# CONNECTOR.net
KiCad netlist of a schematic drawn in Altium Designer
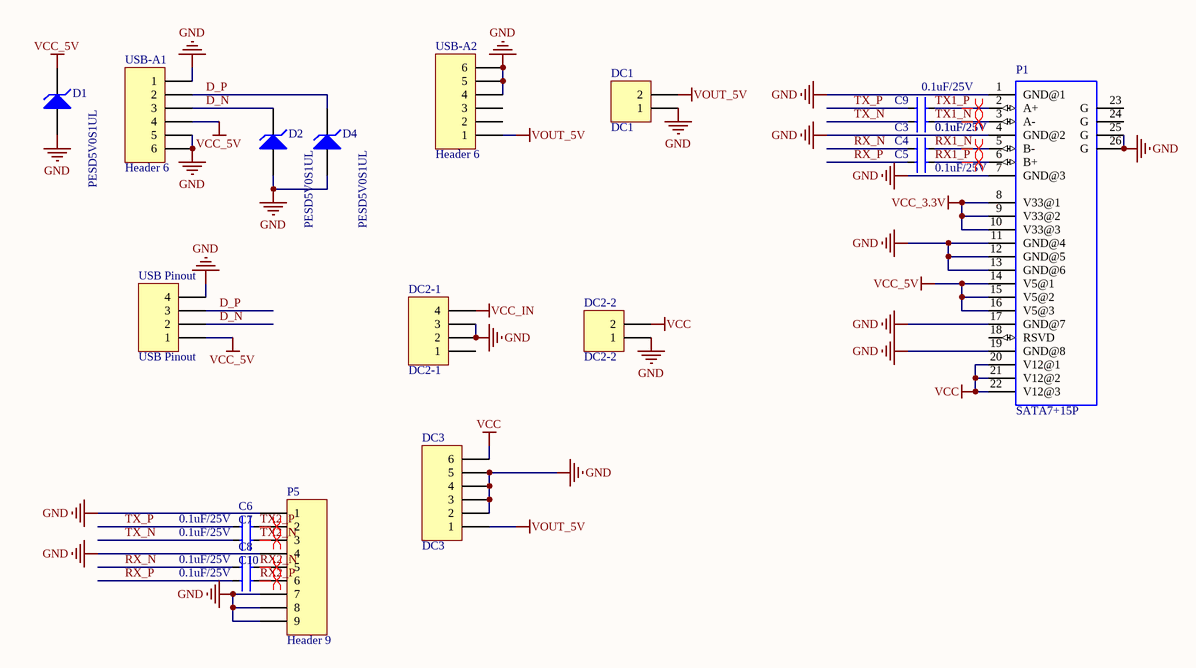
[diagram p0: CONNECTOR.SchDoc]

(export (version "E")
  (design (tool "Eeschema 10.0.6"))
  (components
    (comp (ref "C3")
      (value "0.1uF/25V")
      (footprint "0603C")
      (description "CCX85-103")
      (libsource (lib "无极性电容") (part "0.01UF"))
    )
    (comp (ref "C4")
      (value "0.1uF/25V")
      (footprint "0603C")
      (description "CCX85-103")
      (libsource (lib "无极性电容") (part "0.01UF"))
    )
    (comp (ref "C5")
      (value "0.1uF/25V")
      (footprint "0603C")
      (description "CCX85-103")
      (libsource (lib "无极性电容") (part "0.01UF"))
    )
    (comp (ref "C6")
      (value "0.1uF/25V")
      (footprint "0603C")
      (description "CCX85-103")
      (libsource (lib "无极性电容") (part "0.01UF"))
    )
    (comp (ref "C7")
      (value "0.1uF/25V")
      (footprint "0603C")
      (description "CCX85-103")
      (libsource (lib "无极性电容") (part "0.01UF"))
    )
    (comp (ref "C8")
      (value "0.1uF/25V")
      (footprint "0603C")
      (description "CCX85-103")
      (libsource (lib "无极性电容") (part "0.01UF"))
    )
    (comp (ref "C9")
      (value "0.1uF/25V")
      (footprint "0603C")
      (description "CCX85-103")
      (libsource (lib "无极性电容") (part "0.01UF"))
    )
    (comp (ref "C10")
      (value "0.1uF/25V")
      (footprint "0603C")
      (description "CCX85-103")
      (libsource (lib "无极性电容") (part "0.01UF"))
    )
    (comp (ref "D1")
      (value "PESD5V0S1UL")
      (footprint "0402R")
      (description "Zener Diode")
      (fields (field (name "PUBLISHER") "Altium Limited"))
      (libsource (lib "Miscellaneous Devices") (part "D Zener"))
    )
    (comp (ref "D2")
      (value "PESD5V0S1UL")
      (footprint "0402R")
      (description "Zener Diode")
      (fields (field (name "PUBLISHER") "Altium Limited"))
      (libsource (lib "Miscellaneous Devices") (part "D Zener"))
    )
    (comp (ref "D4")
      (value "PESD5V0S1UL")
      (footprint "0402R")
      (description "Zener Diode")
      (fields (field (name "PUBLISHER") "Altium Limited"))
      (libsource (lib "Miscellaneous Devices") (part "D Zener"))
    )
    (comp (ref "DC1")
      (value "DC1")
      (footprint "2X2MMZ")
      (description "Header, 2-Pin")
      (fields (field (name "PUBLISHER") "Altium Limited"))
      (libsource (lib "Miscellaneous Connectors") (part "Header 2"))
    )
    (comp (ref "DC2-1")
      (value "DC2-1")
      (footprint "DC005")
      (description "Header, 4-Pin")
      (fields (field (name "PUBLISHER") "Altium Limited"))
      (libsource (lib "Miscellaneous Connectors") (part "Header 4"))
    )
    (comp (ref "DC2-2")
      (value "DC2-2")
      (footprint "2X2MMZ")
      (description "Header, 2-Pin")
      (fields (field (name "PUBLISHER") "Altium Limited"))
      (libsource (lib "Miscellaneous Connectors") (part "Header 2"))
    )
    (comp (ref "DC3")
      (value "DC3")
      (footprint "2X6MMZ")
      (description "Header, 6-Pin")
      (fields (field (name "PUBLISHER") "Altium Limited"))
      (libsource (lib "Miscellaneous Connectors") (part "Header 6"))
    )
    (comp (ref "P1")
      (value "SATA7+15P")
      (footprint "SATA 7+15PML")
      (description "Conn SATA PL 15Power/7Signal POS 1.27mm Solder RA Thru-Hole 22 Terminal 1 Port")
      (fields (field (name "MF") "3M") (field (name "MP") "5622-4100-ML"))
      (libsource (lib "Schlib_20110825") (part "SATA7+15P"))
    )
    (comp (ref "P5")
      (value "Header 9")
      (footprint "SATA 7P")
      (description "Header, 9-Pin")
      (fields (field (name "PUBLISHER") "Altium Limited"))
      (libsource (lib "Miscellaneous Connectors") (part "Header 9"))
    )
    (comp (ref "USB Pinout")
      (value "USB Pinout")
      (footprint "sip-4l")
      (description "Header, 4-Pin")
      (fields (field (name "PUBLISHER") "Altium Limited"))
      (libsource (lib "Miscellaneous Connectors") (part "Header 4"))
    )
    (comp (ref "USB-A1")
      (value "Header 6")
      (footprint "USB-A-C")
      (description "Header, 6-Pin")
      (fields (field (name "PUBLISHER") "Altium Limited"))
      (libsource (lib "") (part "Header 6_1"))
    )
    (comp (ref "USB-A2")
      (value "Header 6")
      (footprint "USB-A-C")
      (description "Header, 6-Pin")
      (fields (field (name "PUBLISHER") "Altium Limited"))
      (libsource (lib "Miscellaneous Connectors") (part "Header 6"))
    )
  )
  (nets
    (net (code "1") (name "/D_N") (class "Default")
      (node (ref "D2") (pin "2") (pinfunction "K_2") (pintype "passive"))
      (node (ref "USB Pinout") (pin "2") (pinfunction "2_2") (pintype "passive"))
      (node (ref "USB-A1") (pin "3") (pinfunction "3_3") (pintype "passive"))
    )
    (net (code "2") (name "/D_P") (class "Default")
      (node (ref "D4") (pin "2") (pinfunction "K_2") (pintype "passive"))
      (node (ref "USB Pinout") (pin "3") (pinfunction "3_3") (pintype "passive"))
      (node (ref "USB-A1") (pin "2") (pinfunction "2_2") (pintype "passive"))
    )
    (net (code "3") (name "/RX1_N") (class "Default")
      (node (ref "C4") (pin "2") (pinfunction "2_2") (pintype "passive"))
      (node (ref "P1") (pin "5") (pinfunction "B-_5") (pintype "bidirectional"))
    )
    (net (code "4") (name "/RX1_P") (class "Default")
      (node (ref "C5") (pin "2") (pinfunction "2_2") (pintype "passive"))
      (node (ref "P1") (pin "6") (pinfunction "B+_6") (pintype "bidirectional"))
    )
    (net (code "5") (name "/RX2_N") (class "Default")
      (node (ref "C8") (pin "2") (pinfunction "2_2") (pintype "passive"))
      (node (ref "P5") (pin "5") (pinfunction "5_5") (pintype "passive"))
    )
    (net (code "6") (name "/RX2_P") (class "Default")
      (node (ref "C10") (pin "2") (pinfunction "2_2") (pintype "passive"))
      (node (ref "P5") (pin "6") (pinfunction "6_6") (pintype "passive"))
    )
    (net (code "7") (name "/RX_N") (class "Default")
      (node (ref "C4") (pin "1") (pinfunction "1_1") (pintype "passive"))
      (node (ref "C8") (pin "1") (pinfunction "1_1") (pintype "passive"))
    )
    (net (code "8") (name "/RX_P") (class "Default")
      (node (ref "C10") (pin "1") (pinfunction "1_1") (pintype "passive"))
      (node (ref "C5") (pin "1") (pinfunction "1_1") (pintype "passive"))
    )
    (net (code "9") (name "/TX1_N") (class "Default")
      (node (ref "C3") (pin "2") (pinfunction "2_2") (pintype "passive"))
      (node (ref "P1") (pin "3") (pinfunction "A-_3") (pintype "bidirectional"))
    )
    (net (code "10") (name "/TX1_P") (class "Default")
      (node (ref "C9") (pin "2") (pinfunction "2_2") (pintype "passive"))
      (node (ref "P1") (pin "2") (pinfunction "A+_2") (pintype "bidirectional"))
    )
    (net (code "11") (name "/TX2_N") (class "Default")
      (node (ref "C7") (pin "2") (pinfunction "2_2") (pintype "passive"))
      (node (ref "P5") (pin "3") (pinfunction "3_3") (pintype "passive"))
    )
    (net (code "12") (name "/TX2_P") (class "Default")
      (node (ref "C6") (pin "2") (pinfunction "2_2") (pintype "passive"))
      (node (ref "P5") (pin "2") (pinfunction "2_2") (pintype "passive"))
    )
    (net (code "13") (name "/TX_N") (class "Default")
      (node (ref "C3") (pin "1") (pinfunction "1_1") (pintype "passive"))
      (node (ref "C7") (pin "1") (pinfunction "1_1") (pintype "passive"))
    )
    (net (code "14") (name "/TX_P") (class "Default")
      (node (ref "C6") (pin "1") (pinfunction "1_1") (pintype "passive"))
      (node (ref "C9") (pin "1") (pinfunction "1_1") (pintype "passive"))
    )
    (net (code "15") (name "GND") (class "Default")
      (node (ref "D1") (pin "1") (pinfunction "A_1") (pintype "passive"))
      (node (ref "D2") (pin "1") (pinfunction "A_1") (pintype "passive"))
      (node (ref "D4") (pin "1") (pinfunction "A_1") (pintype "passive"))
      (node (ref "DC1") (pin "1") (pinfunction "1_1") (pintype "passive"))
      (node (ref "DC2-1") (pin "2") (pinfunction "2_2") (pintype "passive"))
      (node (ref "DC2-1") (pin "3") (pinfunction "3_3") (pintype "passive"))
      (node (ref "DC2-2") (pin "1") (pinfunction "1_1") (pintype "passive"))
      (node (ref "DC3") (pin "2") (pinfunction "2_2") (pintype "passive"))
      (node (ref "DC3") (pin "3") (pinfunction "3_3") (pintype "passive"))
      (node (ref "DC3") (pin "4") (pinfunction "4_4") (pintype "passive"))
      (node (ref "DC3") (pin "5") (pinfunction "5_5") (pintype "passive"))
      (node (ref "P1") (pin "1") (pinfunction "GND@1_1") (pintype "power_in"))
      (node (ref "P1") (pin "11") (pinfunction "GND@4_11") (pintype "power_in"))
      (node (ref "P1") (pin "12") (pinfunction "GND@5_12") (pintype "power_in"))
      (node (ref "P1") (pin "13") (pinfunction "GND@6_13") (pintype "power_in"))
      (node (ref "P1") (pin "17") (pinfunction "GND@7_17") (pintype "power_in"))
      (node (ref "P1") (pin "19") (pinfunction "GND@8_19") (pintype "power_in"))
      (node (ref "P1") (pin "25") (pinfunction "G_25") (pintype "power_in"))
      (node (ref "P1") (pin "26") (pinfunction "G_26") (pintype "power_in"))
      (node (ref "P1") (pin "4") (pinfunction "GND@2_4") (pintype "power_in"))
      (node (ref "P1") (pin "7") (pinfunction "GND@3_7") (pintype "power_in"))
      (node (ref "P5") (pin "1") (pinfunction "1_1") (pintype "passive"))
      (node (ref "P5") (pin "4") (pinfunction "4_4") (pintype "passive"))
      (node (ref "P5") (pin "7") (pinfunction "7_7") (pintype "passive"))
      (node (ref "P5") (pin "8") (pinfunction "8_8") (pintype "passive"))
      (node (ref "P5") (pin "9") (pinfunction "9_9") (pintype "passive"))
      (node (ref "USB Pinout") (pin "4") (pinfunction "4_4") (pintype "passive"))
      (node (ref "USB-A1") (pin "1") (pinfunction "1_1") (pintype "passive"))
      (node (ref "USB-A1") (pin "5") (pinfunction "5_5") (pintype "passive"))
      (node (ref "USB-A1") (pin "6") (pinfunction "6_6") (pintype "passive"))
      (node (ref "USB-A2") (pin "4") (pinfunction "4_4") (pintype "passive"))
      (node (ref "USB-A2") (pin "5") (pinfunction "5_5") (pintype "passive"))
      (node (ref "USB-A2") (pin "6") (pinfunction "6_6") (pintype "passive"))
    )
    (net (code "16") (name "VCC") (class "Default")
      (node (ref "DC2-2") (pin "2") (pinfunction "2_2") (pintype "passive"))
      (node (ref "DC3") (pin "6") (pinfunction "6_6") (pintype "passive"))
      (node (ref "P1") (pin "20") (pinfunction "V12@1_20") (pintype "power_in"))
      (node (ref "P1") (pin "21") (pinfunction "V12@2_21") (pintype "power_in"))
      (node (ref "P1") (pin "22") (pinfunction "V12@3_22") (pintype "power_in"))
    )
    (net (code "17") (name "VCC_3.3V") (class "Default")
      (node (ref "P1") (pin "10") (pinfunction "V33@3_10") (pintype "power_in"))
      (node (ref "P1") (pin "8") (pinfunction "V33@1_8") (pintype "power_in"))
      (node (ref "P1") (pin "9") (pinfunction "V33@2_9") (pintype "power_in"))
    )
    (net (code "18") (name "VCC_5V") (class "Default")
      (node (ref "D1") (pin "2") (pinfunction "K_2") (pintype "passive"))
      (node (ref "P1") (pin "14") (pinfunction "V5@1_14") (pintype "power_in"))
      (node (ref "P1") (pin "15") (pinfunction "V5@2_15") (pintype "power_in"))
      (node (ref "P1") (pin "16") (pinfunction "V5@3_16") (pintype "power_in"))
      (node (ref "USB Pinout") (pin "1") (pinfunction "1_1") (pintype "passive"))
      (node (ref "USB-A1") (pin "4") (pinfunction "4_4") (pintype "passive"))
    )
    (net (code "19") (name "VCC_IN") (class "Default")
      (node (ref "DC2-1") (pin "4") (pinfunction "4_4") (pintype "passive"))
    )
    (net (code "20") (name "VOUT_5V") (class "Default")
      (node (ref "DC1") (pin "2") (pinfunction "2_2") (pintype "passive"))
      (node (ref "DC3") (pin "1") (pinfunction "1_1") (pintype "passive"))
      (node (ref "USB-A2") (pin "1") (pinfunction "1_1") (pintype "passive"))
    )
    (net (code "21") (name "unconnected-(DC2-1-Pad1)") (class "Default")
      (node (ref "DC2-1") (pin "1") (pinfunction "1_1") (pintype "passive"))
    )
    (net (code "22") (name "unconnected-(P1-G-Pad23)") (class "Default")
      (node (ref "P1") (pin "23") (pinfunction "G_23") (pintype "power_in"))
    )
    (net (code "23") (name "unconnected-(P1-G-Pad24)") (class "Default")
      (node (ref "P1") (pin "24") (pinfunction "G_24") (pintype "power_in"))
    )
    (net (code "24") (name "unconnected-(P1-RSVD-Pad18)") (class "Default")
      (node (ref "P1") (pin "18") (pinfunction "RSVD_18") (pintype "bidirectional"))
    )
    (net (code "25") (name "unconnected-(USB-A2-Pad2)") (class "Default")
      (node (ref "USB-A2") (pin "2") (pinfunction "2_2") (pintype "passive"))
    )
    (net (code "26") (name "unconnected-(USB-A2-Pad3)") (class "Default")
      (node (ref "USB-A2") (pin "3") (pinfunction "3_3") (pintype "passive"))
    )
  )
)
